# pcb_e2_tp1.net
KiCad netlist of a schematic drawn in Altium Designer
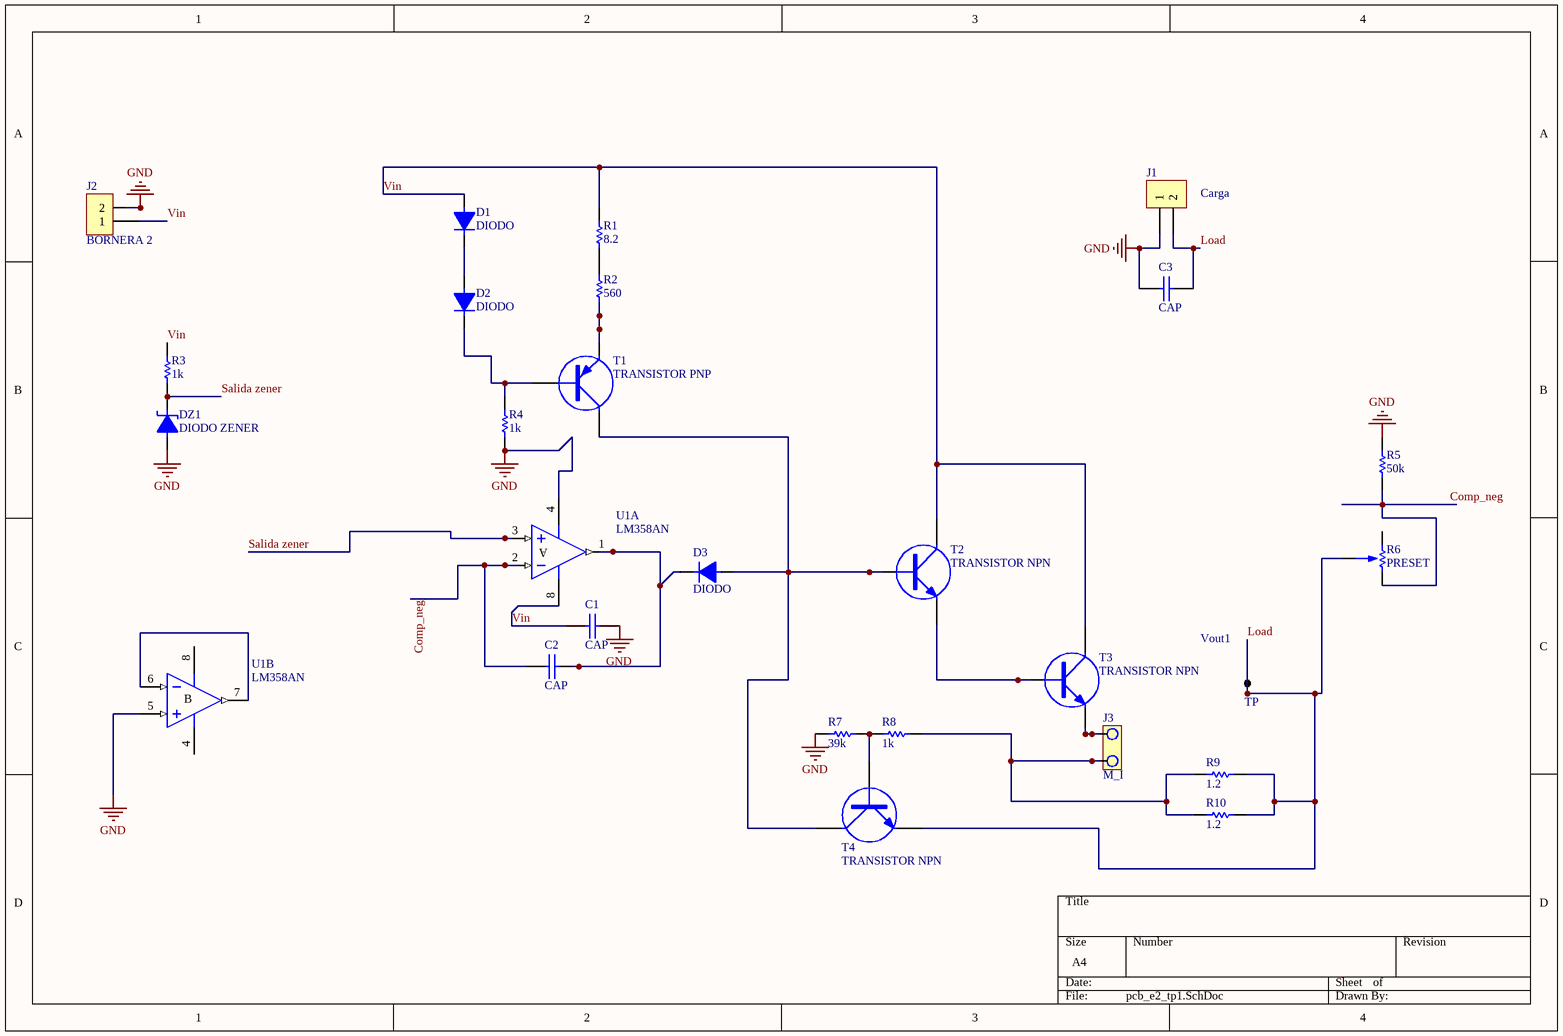
[diagram p0: pcb_e2_tp1.SchDoc]

(export (version "E")
  (design (tool "Eeschema 10.0.6"))
  (components
    (comp (ref "C1") (value "CAP") (footprint "CAP200") (libsource (lib "LIBEBAL") (part "CAP")))
    (comp (ref "C2") (value "CAP") (footprint "CAP200") (libsource (lib "LIBEBAL") (part "CAP")))
    (comp (ref "C3") (value "CAP") (footprint "CAP200") (libsource (lib "LIBEBAL") (part "CAP")))
    (comp (ref "D1") (value "DIODO") (footprint "DO41") (libsource (lib "LIBEBAL") (part "DIODO")))
    (comp (ref "D2") (value "DIODO") (footprint "DO41") (libsource (lib "LIBEBAL") (part "DIODO")))
    (comp (ref "D3") (value "DIODO") (footprint "DO41") (libsource (lib "LIBEBAL") (part "DIODO")))
    (comp (ref "DZ1")
      (value "DIODO ZENER")
      (footprint "DO41")
      (libsource (lib "LIBEBAL") (part "DIODO ZENER"))
    )
    (comp (ref "J1") (value "Carga") (footprint "BORNERA2") (libsource (lib "") (part "BORNERA 2_1")))
    (comp (ref "J2")
      (value "BORNERA 2")
      (footprint "BORNERA2")
      (libsource (lib "LIBEBAL") (part "BORNERA 2"))
    )
    (comp (ref "J3") (value "M_I") (footprint "JUMPER2") (libsource (lib "LIBEBAL") (part "JUMPER")))
    (comp (ref "R1") (value "8.2") (footprint "RES400") (libsource (lib "LIBEBAL") (part "RES")))
    (comp (ref "R2") (value "560") (footprint "RES400") (libsource (lib "LIBEBAL") (part "RES")))
    (comp (ref "R3") (value "1k") (footprint "RES400") (libsource (lib "LIBEBAL") (part "RES")))
    (comp (ref "R4") (value "1k") (footprint "RES400") (libsource (lib "LIBEBAL") (part "RES")))
    (comp (ref "R5") (value "50k") (footprint "RES400") (libsource (lib "LIBEBAL") (part "RES")))
    (comp (ref "R6") (value "PRESET") (footprint "PRESET V") (libsource (lib "LIBEBAL") (part "PRESET")))
    (comp (ref "R7") (value "39k") (footprint "RES400") (libsource (lib "LIBEBAL") (part "RES")))
    (comp (ref "R8") (value "1k") (footprint "RES400") (libsource (lib "LIBEBAL") (part "RES")))
    (comp (ref "R9") (value "1.2") (footprint "RES1200") (libsource (lib "LIBEBAL") (part "RES")))
    (comp (ref "R10") (value "1.2") (footprint "RES1200") (libsource (lib "LIBEBAL") (part "RES")))
    (comp (ref "T1")
      (value "TRANSISTOR PNP")
      (footprint "TO92")
      (libsource (lib "LIBEBAL") (part "TRANSISTOR PNP"))
    )
    (comp (ref "T2")
      (value "TRANSISTOR NPN")
      (footprint "TO92")
      (libsource (lib "LIBEBAL") (part "TRANSISTOR NPN"))
    )
    (comp (ref "T3")
      (value "TRANSISTOR NPN")
      (footprint "TO-220 V")
      (libsource (lib "LIBEBAL") (part "TRANSISTOR NPN"))
    )
    (comp (ref "T4")
      (value "TRANSISTOR NPN")
      (footprint "TO92")
      (libsource (lib "LIBEBAL") (part "TRANSISTOR NPN"))
    )
    (comp (ref "U1")
      (value "LM358AN")
      (footprint "DIP8")
      (description "Low-Power Dual Operational Amplifier")
      (fields (field (name "PUBLISHER") "Altium Limited"))
      (libsource (lib "ST Operational Amplifier") (part "LM358AN"))
    )
    (comp (ref "Vout1") (value "TP") (footprint "TPTH") (libsource (lib "LIBEBAL") (part "TP")))
  )
  (nets
    (net (code "1") (name "/Comp_neg") (class "Default")
      (node (ref "C2") (pin "1") (pinfunction "1_1") (pintype "passive"))
      (node (ref "R5") (pin "1") (pinfunction "1_1") (pintype "passive"))
      (node (ref "R6") (pin "1") (pinfunction "1_1") (pintype "passive"))
      (node (ref "U1") (pin "2") (pinfunction "IN-_2") (pintype "input"))
    )
    (net (code "2") (name "/Load") (class "Default")
      (node (ref "C3") (pin "2") (pinfunction "2_2") (pintype "passive"))
      (node (ref "J1") (pin "2") (pinfunction "2_2") (pintype "passive"))
      (node (ref "R10") (pin "2") (pinfunction "2_2") (pintype "passive"))
      (node (ref "R6") (pin "2") (pinfunction "2_2") (pintype "passive"))
      (node (ref "R9") (pin "2") (pinfunction "2_2") (pintype "passive"))
      (node (ref "T4") (pin "3") (pinfunction "E_3") (pintype "passive"))
      (node (ref "Vout1") (pin "1") (pinfunction "1_1") (pintype "passive"))
    )
    (net (code "3") (name "/Salida zener") (class "Default")
      (node (ref "DZ1") (pin "2") (pinfunction "2_2") (pintype "passive"))
      (node (ref "R3") (pin "1") (pinfunction "1_1") (pintype "passive"))
      (node (ref "U1") (pin "3") (pinfunction "IN+_3") (pintype "input"))
    )
    (net (code "4") (name "/Vin") (class "Default")
      (node (ref "C1") (pin "1") (pinfunction "1_1") (pintype "passive"))
      (node (ref "D1") (pin "1") (pinfunction "1_1") (pintype "passive"))
      (node (ref "J2") (pin "1") (pinfunction "1_1") (pintype "passive"))
      (node (ref "R1") (pin "2") (pinfunction "2_2") (pintype "passive"))
      (node (ref "R3") (pin "2") (pinfunction "2_2") (pintype "passive"))
      (node (ref "T2") (pin "2") (pinfunction "C_2") (pintype "passive"))
      (node (ref "T3") (pin "2") (pinfunction "C_2") (pintype "passive"))
      (node (ref "U1") (pin "8") (pinfunction "V+_8") (pintype "power_in"))
    )
    (net (code "5") (name "GND") (class "Default")
      (node (ref "C1") (pin "2") (pinfunction "2_2") (pintype "passive"))
      (node (ref "C3") (pin "1") (pinfunction "1_1") (pintype "passive"))
      (node (ref "DZ1") (pin "1") (pinfunction "1_1") (pintype "passive"))
      (node (ref "J1") (pin "1") (pinfunction "1_1") (pintype "passive"))
      (node (ref "J2") (pin "2") (pinfunction "2_2") (pintype "passive"))
      (node (ref "R4") (pin "1") (pinfunction "1_1") (pintype "passive"))
      (node (ref "R5") (pin "2") (pinfunction "2_2") (pintype "passive"))
      (node (ref "R7") (pin "1") (pinfunction "1_1") (pintype "passive"))
      (node (ref "U1") (pin "4") (pinfunction "V-_4") (pintype "power_in"))
      (node (ref "U1") (pin "5") (pinfunction "IN+_5") (pintype "input"))
    )
    (net (code "6") (name "Net-(D1-Pad2)") (class "Default")
      (node (ref "D1") (pin "2") (pinfunction "2_2") (pintype "passive"))
      (node (ref "D2") (pin "1") (pinfunction "1_1") (pintype "passive"))
    )
    (net (code "7") (name "Net-(J3-Pad1)") (class "Default")
      (node (ref "J3") (pin "1") (pinfunction "1_1") (pintype "passive"))
      (node (ref "R10") (pin "1") (pinfunction "1_1") (pintype "passive"))
      (node (ref "R8") (pin "2") (pinfunction "2_2") (pintype "passive"))
      (node (ref "R9") (pin "1") (pinfunction "1_1") (pintype "passive"))
    )
    (net (code "8") (name "Net-(R1-Pad1)") (class "Default")
      (node (ref "R1") (pin "1") (pinfunction "1_1") (pintype "passive"))
      (node (ref "R2") (pin "2") (pinfunction "2_2") (pintype "passive"))
    )
    (net (code "9") (name "Net-(T1-B)") (class "Default")
      (node (ref "D2") (pin "2") (pinfunction "2_2") (pintype "passive"))
      (node (ref "R4") (pin "2") (pinfunction "2_2") (pintype "passive"))
      (node (ref "T1") (pin "1") (pinfunction "B_1") (pintype "passive"))
    )
    (net (code "10") (name "Net-(T1-C)") (class "Default")
      (node (ref "D3") (pin "1") (pinfunction "1_1") (pintype "passive"))
      (node (ref "T1") (pin "2") (pinfunction "C_2") (pintype "passive"))
      (node (ref "T2") (pin "1") (pinfunction "B_1") (pintype "passive"))
      (node (ref "T4") (pin "2") (pinfunction "C_2") (pintype "passive"))
    )
    (net (code "11") (name "Net-(T1-E)") (class "Default")
      (node (ref "R2") (pin "1") (pinfunction "1_1") (pintype "passive"))
      (node (ref "T1") (pin "3") (pinfunction "E_3") (pintype "passive"))
    )
    (net (code "12") (name "Net-(T2-E)") (class "Default")
      (node (ref "T2") (pin "3") (pinfunction "E_3") (pintype "passive"))
      (node (ref "T3") (pin "1") (pinfunction "B_1") (pintype "passive"))
    )
    (net (code "13") (name "Net-(T3-E)") (class "Default")
      (node (ref "J3") (pin "2") (pinfunction "2_2") (pintype "passive"))
      (node (ref "T3") (pin "3") (pinfunction "E_3") (pintype "passive"))
    )
    (net (code "14") (name "Net-(T4-B)") (class "Default")
      (node (ref "R7") (pin "2") (pinfunction "2_2") (pintype "passive"))
      (node (ref "R8") (pin "1") (pinfunction "1_1") (pintype "passive"))
      (node (ref "T4") (pin "1") (pinfunction "B_1") (pintype "passive"))
    )
    (net (code "15") (name "Net-(U1A-OUT)") (class "Default")
      (node (ref "C2") (pin "2") (pinfunction "2_2") (pintype "passive"))
      (node (ref "D3") (pin "2") (pinfunction "2_2") (pintype "passive"))
      (node (ref "U1") (pin "1") (pinfunction "OUT_1") (pintype "output"))
    )
    (net (code "16") (name "Net-(U1B-IN-)") (class "Default")
      (node (ref "U1") (pin "6") (pinfunction "IN-_6") (pintype "input"))
      (node (ref "U1") (pin "7") (pinfunction "OUT_7") (pintype "output"))
    )
    (net (code "17") (name "unconnected-(R6-Pad3)") (class "Default")
      (node (ref "R6") (pin "3") (pinfunction "3_3") (pintype "passive"))
    )
    (net (code "18") (name "unconnected-(U1B-V+-Pad8)") (class "Default")
      (node (ref "U1") (pin "8") (pinfunction "V+_8") (pintype "power_in"))
    )
    (net (code "19") (name "unconnected-(U1B-V--Pad4)") (class "Default")
      (node (ref "U1") (pin "4") (pinfunction "V-_4") (pintype "power_in"))
    )
  )
)
